# PATHOS_FPGA_Clk.net
KiCad netlist of a schematic drawn in Altium Designer
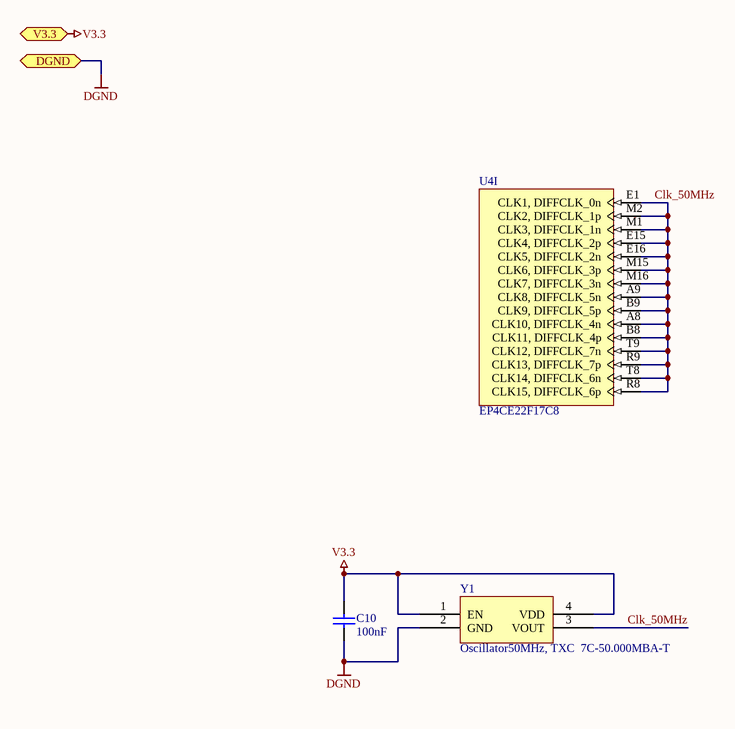
[diagram p0: PATHOS_FPGA_Clk.SchDoc]

(export (version "E")
  (design (tool "Eeschema 10.0.6"))
  (components
    (comp (ref "C10")
      (value "100nF")
      (footprint "Pathos:0603_3D")
      (description "Capacitor")
      (fields (field (name "#PUBLISHER") "Dr. A. Heinzelmann"))
      (libsource (lib "EFS_Sensorboard") (part "C"))
    )
    (comp (ref "U4")
      (value "EP4CE22F17C8")
      (footprint "FBGA256")
      (fields (field (name "PUBLISHER") "Altium Limited"))
      (libsource (lib "EFS_Sensorboard") (part "EP4CE22F17C8"))
    )
    (comp (ref "Y1")
      (value "Oscillator50MHz, TXC  7C-50.000MBA-T")
      (footprint "Pathos:OSC_50MHz_TXC")
      (libsource (lib "EFSSensorboard_1") (part "Oscillator50MHz"))
    )
  )
  (nets
    (net (code "1") (name "/Clk_50MHz") (class "Default")
      (node (ref "U4") (pin "A8") (pinfunction "CLK10,_DIFFCLK_4n_A8") (pintype "input"))
      (node (ref "U4") (pin "A9") (pinfunction "CLK8,_DIFFCLK_5n_A9") (pintype "input"))
      (node (ref "U4") (pin "B8") (pinfunction "CLK11,_DIFFCLK_4p_B8") (pintype "input"))
      (node (ref "U4") (pin "B9") (pinfunction "CLK9,_DIFFCLK_5p_B9") (pintype "input"))
      (node (ref "U4") (pin "E1") (pinfunction "CLK1,_DIFFCLK_0n_E1") (pintype "input"))
      (node (ref "U4") (pin "E15") (pinfunction "CLK4,_DIFFCLK_2p_E15") (pintype "input"))
      (node (ref "U4") (pin "E16") (pinfunction "CLK5,_DIFFCLK_2n_E16") (pintype "input"))
      (node (ref "U4") (pin "M1") (pinfunction "CLK3,_DIFFCLK_1n_M1") (pintype "input"))
      (node (ref "U4") (pin "M15") (pinfunction "CLK6,_DIFFCLK_3p_M15") (pintype "input"))
      (node (ref "U4") (pin "M16") (pinfunction "CLK7,_DIFFCLK_3n_M16") (pintype "input"))
      (node (ref "U4") (pin "M2") (pinfunction "CLK2,_DIFFCLK_1p_M2") (pintype "input"))
      (node (ref "U4") (pin "R8") (pinfunction "CLK15,_DIFFCLK_6p_R8") (pintype "input"))
      (node (ref "U4") (pin "R9") (pinfunction "CLK13,_DIFFCLK_7p_R9") (pintype "input"))
      (node (ref "U4") (pin "T8") (pinfunction "CLK14,_DIFFCLK_6n_T8") (pintype "input"))
      (node (ref "U4") (pin "T9") (pinfunction "CLK12,_DIFFCLK_7n_T9") (pintype "input"))
      (node (ref "Y1") (pin "3") (pinfunction "VOUT_3") (pintype "passive"))
    )
    (net (code "2") (name "DGND") (class "Default")
      (node (ref "C10") (pin "1") (pinfunction "1_1") (pintype "passive"))
      (node (ref "Y1") (pin "2") (pinfunction "GND_2") (pintype "passive"))
    )
    (net (code "3") (name "V3.3") (class "Default")
      (node (ref "C10") (pin "2") (pinfunction "2_2") (pintype "passive"))
      (node (ref "Y1") (pin "1") (pinfunction "EN_1") (pintype "passive"))
      (node (ref "Y1") (pin "4") (pinfunction "VDD_4") (pintype "passive"))
    )
  )
)
